# PROC106B_CAN_INTERFACE.net
KiCad netlist of a schematic drawn in Altium Designer
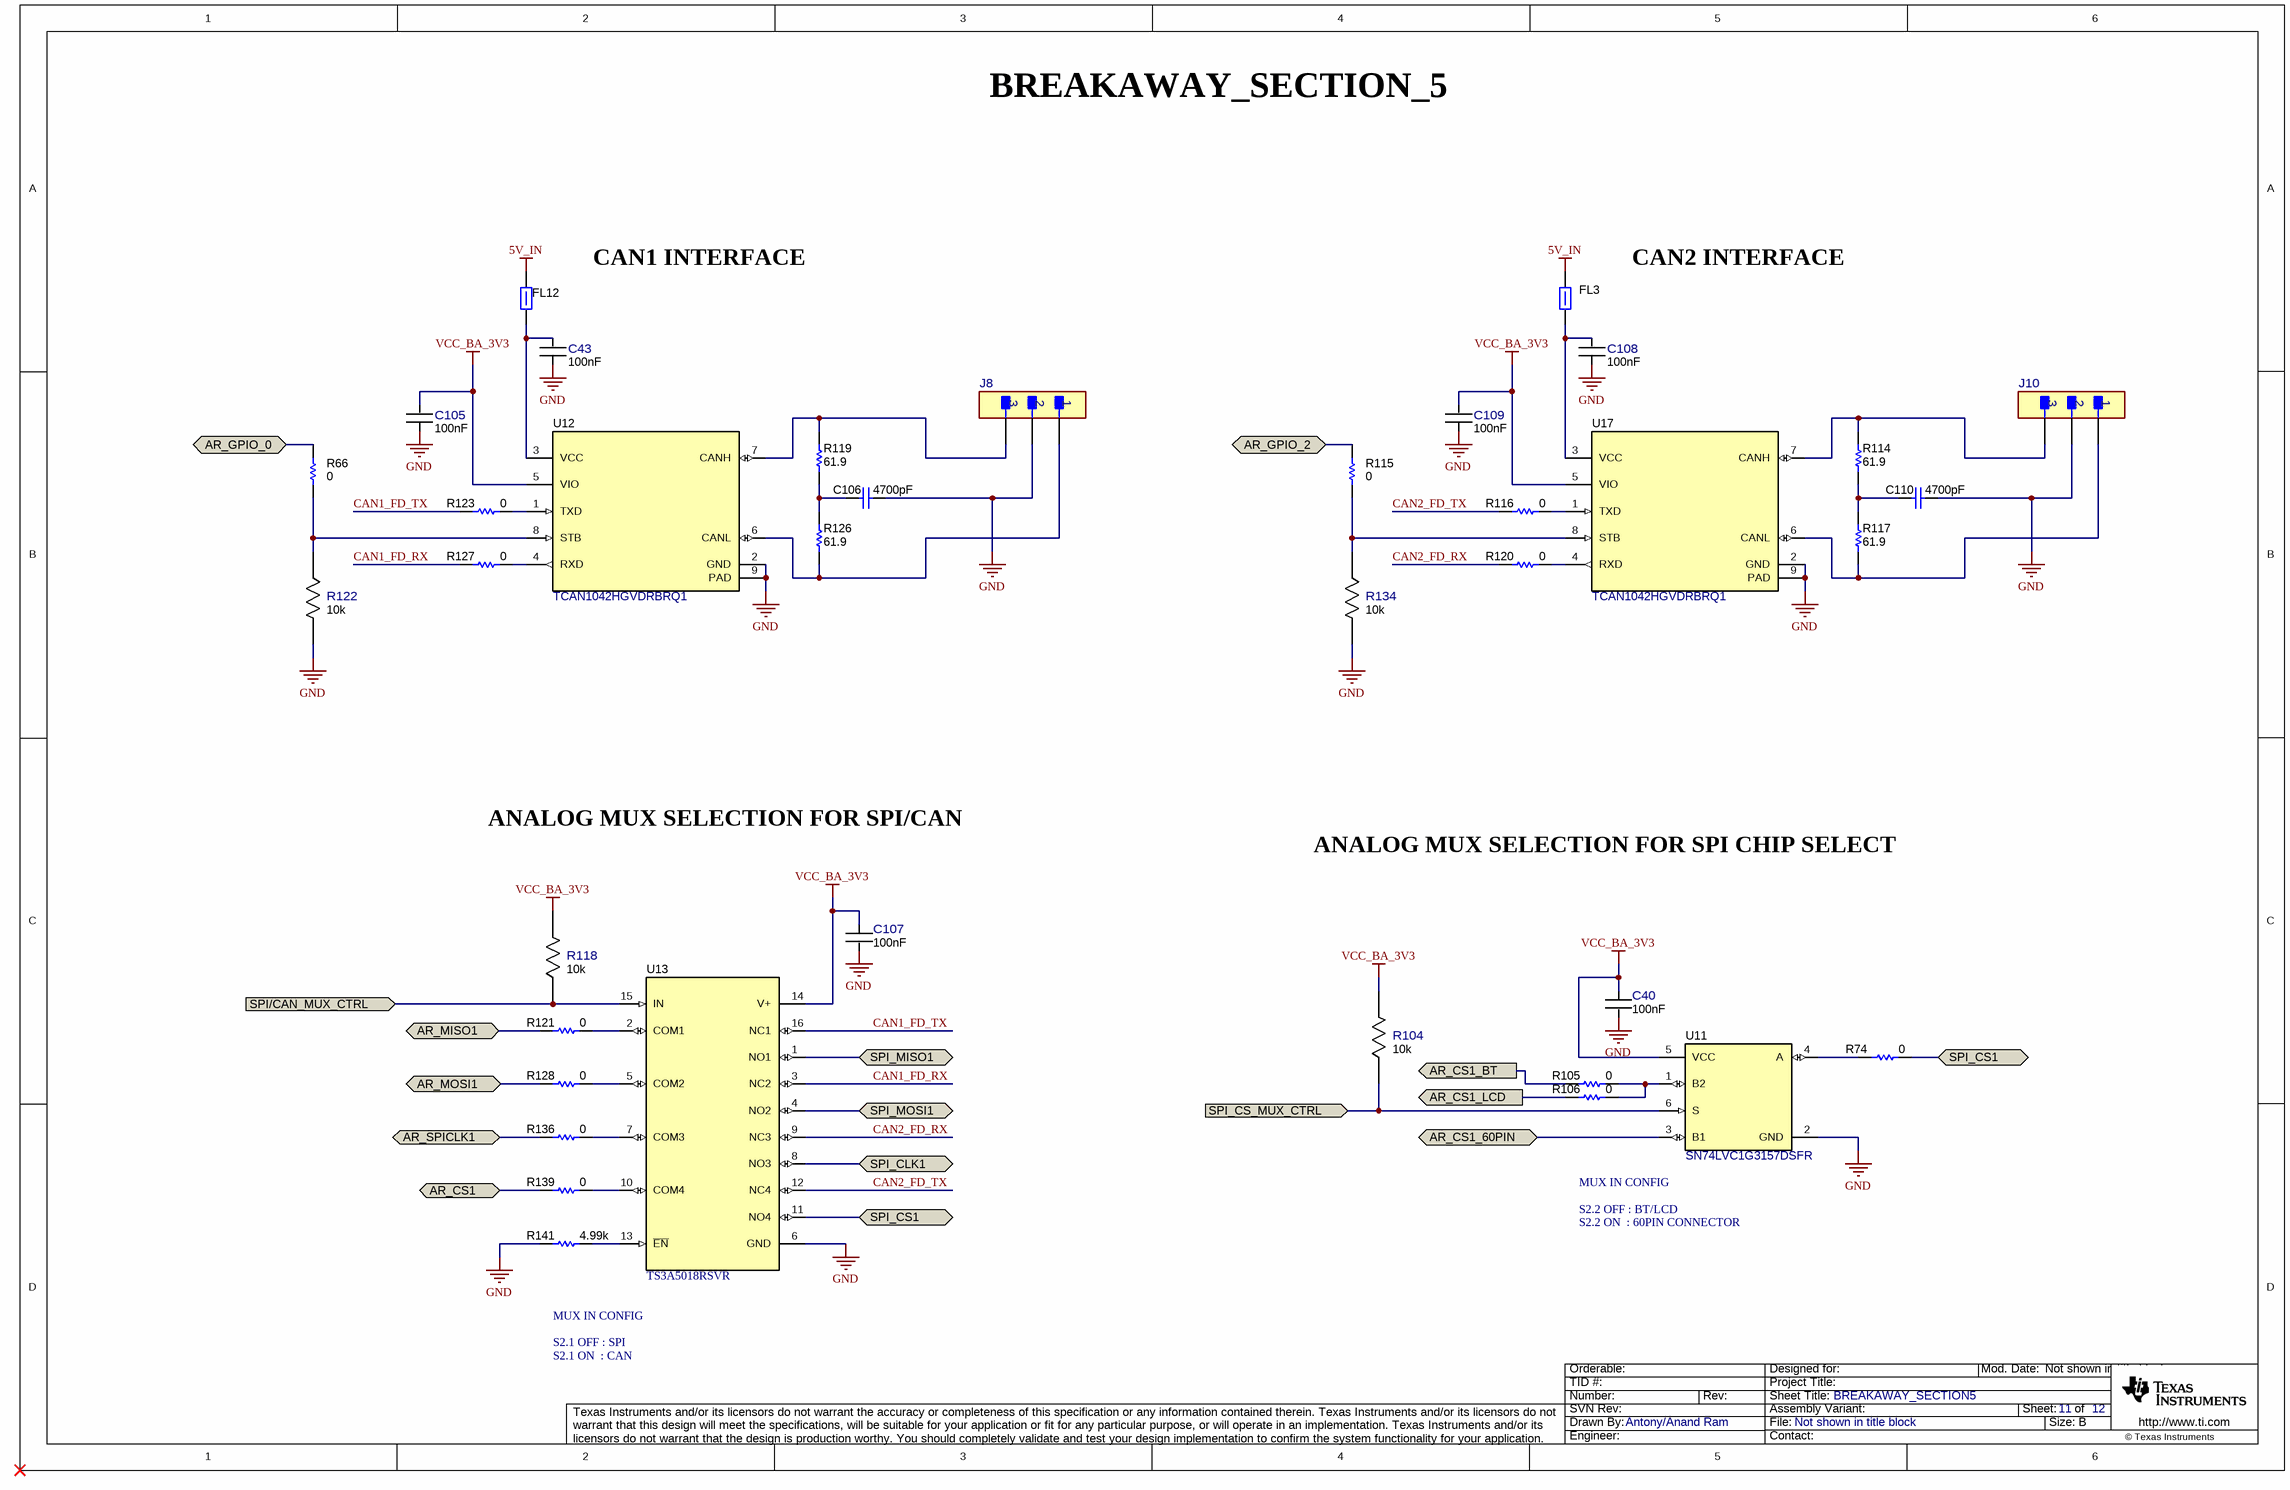
[diagram p0: PROC106B_CAN_INTERFACE.SchDoc]

(export (version "E")
  (design (tool "Eeschema 10.0.6"))
  (components
    (comp (ref "C40")
      (value "GRM033R6YA104KE14D")
      (footprint "FP-GRM033R6YA104KE14D_0201 (0603 Metric)-IPC_C")
      (description "Cap Ceramic 0.1uF 35V X5R 10% Pad SMD 0201 85C T/R")
      (fields (field (name "CAP_F") "100nF") (field (name "MANUFACTURER") "Murata Electronics North America"))
      (libsource (lib "Altium Vault - TI") (part "SYM-B32642B0223J"))
    )
    (comp (ref "C43")
      (value "GRM033R6YA104KE14D")
      (footprint "FP-GRM033R6YA104KE14D_0201 (0603 Metric)-IPC_C")
      (description "Cap Ceramic 0.1uF 35V X5R 10% Pad SMD 0201 85C T/R")
      (fields (field (name "CAP_F") "100nF") (field (name "MANUFACTURER") "Murata Electronics North America"))
      (libsource (lib "Altium Vault - TI") (part "SYM-B32642B0223J"))
    )
    (comp (ref "C105")
      (value "GRM033R6YA104KE14D")
      (footprint "FP-GRM033R6YA104KE14D_0201 (0603 Metric)-IPC_C")
      (description "Cap Ceramic 0.1uF 35V X5R 10% Pad SMD 0201 85C T/R")
      (fields (field (name "CAP_F") "100nF") (field (name "MANUFACTURER") "Murata Electronics North America"))
      (libsource (lib "Altium Vault - TI") (part "SYM-B32642B0223J"))
    )
    (comp (ref "C106")
      (value "GRM155R71H472KA01D")
      (footprint "0402L")
      (description "CAP, CERM, 4700 pF, 50 V, +/- 10%, X7R, 0402")
      (fields
        (field (name "MANUFACTURER") "MuRata")
        (field (name "VALUEDISPLAYED") "4700pF")
        (field (name "PUBLISHER") "Texas Instruments")
      )
      (libsource (lib "Altium Vault - TI") (part "Capacitor"))
    )
    (comp (ref "C107")
      (value "GRM033R6YA104KE14D")
      (footprint "FP-GRM033R6YA104KE14D_0201 (0603 Metric)-IPC_C")
      (description "Cap Ceramic 0.1uF 35V X5R 10% Pad SMD 0201 85C T/R")
      (fields (field (name "CAP_F") "100nF") (field (name "MANUFACTURER") "Murata Electronics North America"))
      (libsource (lib "Altium Vault - TI") (part "SYM-B32642B0223J"))
    )
    (comp (ref "C108")
      (value "GRM033R6YA104KE14D")
      (footprint "FP-GRM033R6YA104KE14D_0201 (0603 Metric)-IPC_C")
      (description "Cap Ceramic 0.1uF 35V X5R 10% Pad SMD 0201 85C T/R")
      (fields (field (name "CAP_F") "100nF") (field (name "MANUFACTURER") "Murata Electronics North America"))
      (libsource (lib "Altium Vault - TI") (part "SYM-B32642B0223J"))
    )
    (comp (ref "C109")
      (value "GRM033R6YA104KE14D")
      (footprint "FP-GRM033R6YA104KE14D_0201 (0603 Metric)-IPC_C")
      (description "Cap Ceramic 0.1uF 35V X5R 10% Pad SMD 0201 85C T/R")
      (fields (field (name "CAP_F") "100nF") (field (name "MANUFACTURER") "Murata Electronics North America"))
      (libsource (lib "Altium Vault - TI") (part "SYM-B32642B0223J"))
    )
    (comp (ref "C110")
      (value "GRM155R71H472KA01D")
      (footprint "0402L")
      (description "CAP, CERM, 4700 pF, 50 V, +/- 10%, X7R, 0402")
      (fields
        (field (name "MANUFACTURER") "MuRata")
        (field (name "VALUEDISPLAYED") "4700pF")
        (field (name "PUBLISHER") "Texas Instruments")
      )
      (libsource (lib "Altium Vault - TI") (part "Capacitor"))
    )
    (comp (ref "FL3")
      (value "BLM15PD300SZ1D")
      (footprint "0402L")
      (description "Inductor, Ferrite Bead, Ferrite, 2.2 A, 0.035 ohm, AEC-Q200 Grade 1, SMD")
      (fields (field (name "MANUFACTURER") "MuRata") (field (name "PUBLISHER") "Texas Instruments"))
      (libsource (lib "Altium Vault - TI") (part "Ferrite_Bead"))
    )
    (comp (ref "FL12")
      (value "BLM15PD300SZ1D")
      (footprint "0402L")
      (description "Inductor, Ferrite Bead, Ferrite, 2.2 A, 0.035 ohm, AEC-Q200 Grade 1, SMD")
      (fields (field (name "MANUFACTURER") "MuRata") (field (name "PUBLISHER") "Texas Instruments"))
      (libsource (lib "Altium Vault - TI") (part "Ferrite_Bead"))
    )
    (comp (ref "J8")
      (value "M50-3930342")
      (footprint "FP-M50-3930342_HDR3-MFG")
      (description "CONN HEADER R/A 3POS 1.27MM")
      (fields (field (name "MANUFACTURER") "Harwin"))
      (libsource (lib "Altium Vault - TI") (part "SYM-M50-3930342"))
    )
    (comp (ref "J10")
      (value "M50-3930342")
      (footprint "FP-M50-3930342_HDR3-MFG")
      (description "CONN HEADER R/A 3POS 1.27MM")
      (fields (field (name "MANUFACTURER") "Harwin"))
      (libsource (lib "Altium Vault - TI") (part "SYM-M50-3930342"))
    )
    (comp (ref "R66")
      (value "RC0201JR-070RL")
      (footprint "FP-RC0201JR-070RL_0201 (0603 Metric)-IPC_C")
      (description "RES SMD 0 OHM JUMPER 1/20W 0201")
      (fields (field (name "MANUFACTURER") "Yageo") (field (name "RES_OHM") "0"))
      (libsource (lib "Altium Vault - TI") (part "SYM-WSR3R1500F"))
    )
    (comp (ref "R74")
      (value "RC0201JR-070RL")
      (footprint "FP-RC0201JR-070RL_0201 (0603 Metric)-IPC_C")
      (description "RES SMD 0 OHM JUMPER 1/20W 0201")
      (fields (field (name "MANUFACTURER") "Yageo") (field (name "RES_OHM") "0"))
      (libsource (lib "Altium Vault - TI") (part "SYM-WSR3R1500F"))
    )
    (comp (ref "R104")
      (value "RR0306P-103-D")
      (footprint "FP-RR0306P-103-D_0201-IPC_C")
      (description "10 kOhms ±0.5% 0.05W, 1/20W Chip Resistor 0201 (0603 Metric)  Thin Film")
      (fields (field (name "MANUFACTURER") "Susumu") (field (name "RES_OHM") "10k"))
      (libsource (lib "Altium Vault - TI") (part "SYM-PMR18EZPJ000"))
    )
    (comp (ref "R105")
      (value "RC0201JR-070RL")
      (footprint "FP-RC0201JR-070RL_0201 (0603 Metric)-IPC_C")
      (description "RES SMD 0 OHM JUMPER 1/20W 0201")
      (fields (field (name "MANUFACTURER") "Yageo") (field (name "RES_OHM") "0"))
      (libsource (lib "Altium Vault - TI") (part "SYM-WSR3R1500F"))
    )
    (comp (ref "R106")
      (value "RC0201JR-070RL")
      (footprint "FP-RC0201JR-070RL_0201 (0603 Metric)-IPC_C")
      (description "RES SMD 0 OHM JUMPER 1/20W 0201")
      (fields (field (name "MANUFACTURER") "Yageo") (field (name "RES_OHM") "0"))
      (libsource (lib "Altium Vault - TI") (part "SYM-WSR3R1500F"))
    )
    (comp (ref "R114")
      (value "CRCW040261R9FKED")
      (footprint "0402L")
      (description "RES, 61.9, 1%, 0.063 W, AEC-Q200 Grade 0, 0402")
      (fields (field (name "MANUFACTURER") "Vishay-Dale") (field (name "VALUEDISPLAYED") "61.9"))
      (libsource (lib "Altium Vault - TI") (part "Resistor"))
    )
    (comp (ref "R115")
      (value "RC0201JR-070RL")
      (footprint "FP-RC0201JR-070RL_0201 (0603 Metric)-IPC_C")
      (description "RES SMD 0 OHM JUMPER 1/20W 0201")
      (fields (field (name "MANUFACTURER") "Yageo") (field (name "RES_OHM") "0"))
      (libsource (lib "Altium Vault - TI") (part "SYM-WSR3R1500F"))
    )
    (comp (ref "R116")
      (value "RC0201JR-070RL")
      (footprint "FP-RC0201JR-070RL_0201 (0603 Metric)-IPC_C")
      (description "RES SMD 0 OHM JUMPER 1/20W 0201")
      (fields (field (name "MANUFACTURER") "Yageo") (field (name "RES_OHM") "0"))
      (libsource (lib "Altium Vault - TI") (part "SYM-WSR3R1500F"))
    )
    (comp (ref "R117")
      (value "CRCW040261R9FKED")
      (footprint "0402L")
      (description "RES, 61.9, 1%, 0.063 W, AEC-Q200 Grade 0, 0402")
      (fields (field (name "MANUFACTURER") "Vishay-Dale") (field (name "VALUEDISPLAYED") "61.9"))
      (libsource (lib "Altium Vault - TI") (part "Resistor"))
    )
    (comp (ref "R118")
      (value "RR0306P-103-D")
      (footprint "FP-RR0306P-103-D_0201-IPC_C")
      (description "10 kOhms ±0.5% 0.05W, 1/20W Chip Resistor 0201 (0603 Metric)  Thin Film")
      (fields (field (name "MANUFACTURER") "Susumu") (field (name "RES_OHM") "10k"))
      (libsource (lib "Altium Vault - TI") (part "SYM-PMR18EZPJ000"))
    )
    (comp (ref "R119")
      (value "CRCW040261R9FKED")
      (footprint "0402L")
      (description "RES, 61.9, 1%, 0.063 W, AEC-Q200 Grade 0, 0402")
      (fields (field (name "MANUFACTURER") "Vishay-Dale") (field (name "VALUEDISPLAYED") "61.9"))
      (libsource (lib "Altium Vault - TI") (part "Resistor"))
    )
    (comp (ref "R120")
      (value "RC0201JR-070RL")
      (footprint "FP-RC0201JR-070RL_0201 (0603 Metric)-IPC_C")
      (description "RES SMD 0 OHM JUMPER 1/20W 0201")
      (fields (field (name "MANUFACTURER") "Yageo") (field (name "RES_OHM") "0"))
      (libsource (lib "Altium Vault - TI") (part "SYM-WSR3R1500F"))
    )
    (comp (ref "R121")
      (value "RC0201JR-070RL")
      (footprint "FP-RC0201JR-070RL_0201 (0603 Metric)-IPC_C")
      (description "RES SMD 0 OHM JUMPER 1/20W 0201")
      (fields (field (name "MANUFACTURER") "Yageo") (field (name "RES_OHM") "0"))
      (libsource (lib "Altium Vault - TI") (part "SYM-WSR3R1500F"))
    )
    (comp (ref "R122")
      (value "RR0306P-103-D")
      (footprint "FP-RR0306P-103-D_0201-IPC_C")
      (description "10 kOhms ±0.5% 0.05W, 1/20W Chip Resistor 0201 (0603 Metric)  Thin Film")
      (fields (field (name "MANUFACTURER") "Susumu") (field (name "RES_OHM") "10k"))
      (libsource (lib "Altium Vault - TI") (part "SYM-PMR18EZPJ000"))
    )
    (comp (ref "R123")
      (value "RC0201JR-070RL")
      (footprint "FP-RC0201JR-070RL_0201 (0603 Metric)-IPC_C")
      (description "RES SMD 0 OHM JUMPER 1/20W 0201")
      (fields (field (name "MANUFACTURER") "Yageo") (field (name "RES_OHM") "0"))
      (libsource (lib "Altium Vault - TI") (part "SYM-WSR3R1500F"))
    )
    (comp (ref "R126")
      (value "CRCW040261R9FKED")
      (footprint "0402L")
      (description "RES, 61.9, 1%, 0.063 W, AEC-Q200 Grade 0, 0402")
      (fields (field (name "MANUFACTURER") "Vishay-Dale") (field (name "VALUEDISPLAYED") "61.9"))
      (libsource (lib "Altium Vault - TI") (part "Resistor"))
    )
    (comp (ref "R127")
      (value "RC0201JR-070RL")
      (footprint "FP-RC0201JR-070RL_0201 (0603 Metric)-IPC_C")
      (description "RES SMD 0 OHM JUMPER 1/20W 0201")
      (fields (field (name "MANUFACTURER") "Yageo") (field (name "RES_OHM") "0"))
      (libsource (lib "Altium Vault - TI") (part "SYM-WSR3R1500F"))
    )
    (comp (ref "R128")
      (value "RC0201JR-070RL")
      (footprint "FP-RC0201JR-070RL_0201 (0603 Metric)-IPC_C")
      (description "RES SMD 0 OHM JUMPER 1/20W 0201")
      (fields (field (name "MANUFACTURER") "Yageo") (field (name "RES_OHM") "0"))
      (libsource (lib "Altium Vault - TI") (part "SYM-WSR3R1500F"))
    )
    (comp (ref "R134")
      (value "RR0306P-103-D")
      (footprint "FP-RR0306P-103-D_0201-IPC_C")
      (description "10 kOhms ±0.5% 0.05W, 1/20W Chip Resistor 0201 (0603 Metric)  Thin Film")
      (fields (field (name "MANUFACTURER") "Susumu") (field (name "RES_OHM") "10k"))
      (libsource (lib "Altium Vault - TI") (part "SYM-PMR18EZPJ000"))
    )
    (comp (ref "R136")
      (value "RC0201JR-070RL")
      (footprint "FP-RC0201JR-070RL_0201 (0603 Metric)-IPC_C")
      (description "RES SMD 0 OHM JUMPER 1/20W 0201")
      (fields (field (name "MANUFACTURER") "Yageo") (field (name "RES_OHM") "0"))
      (libsource (lib "Altium Vault - TI") (part "SYM-WSR3R1500F"))
    )
    (comp (ref "R139")
      (value "RC0201JR-070RL")
      (footprint "FP-RC0201JR-070RL_0201 (0603 Metric)-IPC_C")
      (description "RES SMD 0 OHM JUMPER 1/20W 0201")
      (fields (field (name "MANUFACTURER") "Yageo") (field (name "RES_OHM") "0"))
      (libsource (lib "Altium Vault - TI") (part "SYM-WSR3R1500F"))
    )
    (comp (ref "R141")
      (value "4.99k")
      (footprint "0201L")
      (description "RES, 4.99 k, 1%, 0.05 W, 0201")
      (fields
        (field (name "MANUFACTURER") "Yageo America")
        (field (name "PARTNUMBER") "RC0201FR-074K99L")
        (field (name "PUBLISHER") "Texas Instruments")
      )
      (libsource (lib "Altium Vault - TI") (part "Resistor"))
    )
    (comp (ref "U11")
      (value "SN74LVC1G3157DSFR")
      (footprint "DSF0006A")
      (description "1-Channel, 2:1 Analog Switch, DSF0006A (X2SON-6)")
      (fields
        (field (name "GENERIC PART NUMBER") "SN74LVC1G3157")
        (field (name "MANUFACTURER") "Texas Instruments")
      )
      (libsource (lib "Altium Vault - TI") (part "SN74LVC1G3157"))
    )
    (comp (ref "U12")
      (value "TCAN1042HGVDRBRQ1")
      (footprint "DRB0008F")
      (description "Automotive Fault Protected CAN Transceiver With Flexible Data-Rate, DRB0008F (VSON-8)")
      (fields
        (field (name "MANUFACTURER") "Texas Instruments")
        (field (name "ALTERNATE PARTNUMBER") "TCAN1042HGVDRBTQ1")
      )
      (libsource (lib "Altium Vault - TI") (part "TCAN1042DRB_V"))
    )
    (comp (ref "U13")
      (value "TS3A5018RSVR")
      (footprint "RSV0016A")
      (description "10-Ohm Quad SPDT Analog Switch, RSV0016A (UQFN-16)")
      (fields
        (field (name "MANUFACTURER") "Texas Instruments")
        (field (name "PARTNUMBER") "TS3A5018RSVR")
        (field (name "PUBLISHER") "Texas Instruments")
      )
      (libsource (lib "Altium Vault - TI") (part "TS3A5018RSV"))
    )
    (comp (ref "U17")
      (value "TCAN1042HGVDRBRQ1")
      (footprint "DRB0008F")
      (description "Automotive Fault Protected CAN Transceiver With Flexible Data-Rate, DRB0008F (VSON-8)")
      (fields
        (field (name "MANUFACTURER") "Texas Instruments")
        (field (name "ALTERNATE PARTNUMBER") "TCAN1042HGVDRBTQ1")
      )
      (libsource (lib "Altium Vault - TI") (part "TCAN1042DRB_V"))
    )
  )
  (nets
    (net (code "1") (name "/AR_CS1") (class "Default")
      (node (ref "R139") (pin "2") (pinfunction "2_2") (pintype "passive"))
    )
    (net (code "2") (name "/AR_CS1_60PIN") (class "Default")
      (node (ref "U11") (pin "3") (pinfunction "B1_3") (pintype "bidirectional"))
    )
    (net (code "3") (name "/AR_CS1_BT") (class "Default")
      (node (ref "R105") (pin "2") (pinfunction "2_2") (pintype "passive"))
    )
    (net (code "4") (name "/AR_CS1_LCD") (class "Default")
      (node (ref "R106") (pin "2") (pinfunction "2_2") (pintype "passive"))
    )
    (net (code "5") (name "/AR_GPIO_0") (class "Default")
      (node (ref "R66") (pin "1") (pinfunction "1_1") (pintype "passive"))
    )
    (net (code "6") (name "/AR_GPIO_2") (class "Default")
      (node (ref "R115") (pin "1") (pinfunction "1_1") (pintype "passive"))
    )
    (net (code "7") (name "/AR_MISO1") (class "Default")
      (node (ref "R121") (pin "2") (pinfunction "2_2") (pintype "passive"))
    )
    (net (code "8") (name "/AR_MOSI1") (class "Default")
      (node (ref "R128") (pin "2") (pinfunction "2_2") (pintype "passive"))
    )
    (net (code "9") (name "/AR_SPICLK1") (class "Default")
      (node (ref "R136") (pin "2") (pinfunction "2_2") (pintype "passive"))
    )
    (net (code "10") (name "/CAN1_FD_RX") (class "Default")
      (node (ref "R127") (pin "2") (pinfunction "2_2") (pintype "passive"))
      (node (ref "U13") (pin "3") (pinfunction "NC2_3") (pintype "bidirectional"))
    )
    (net (code "11") (name "/CAN1_FD_TX") (class "Default")
      (node (ref "R123") (pin "2") (pinfunction "2_2") (pintype "passive"))
      (node (ref "U13") (pin "16") (pinfunction "NC1_16") (pintype "bidirectional"))
    )
    (net (code "12") (name "/CAN2_FD_RX") (class "Default")
      (node (ref "R120") (pin "2") (pinfunction "2_2") (pintype "passive"))
      (node (ref "U13") (pin "9") (pinfunction "NC3_9") (pintype "bidirectional"))
    )
    (net (code "13") (name "/CAN2_FD_TX") (class "Default")
      (node (ref "R116") (pin "2") (pinfunction "2_2") (pintype "passive"))
      (node (ref "U13") (pin "12") (pinfunction "NC4_12") (pintype "bidirectional"))
    )
    (net (code "14") (name "/SPI_CLK1") (class "Default")
      (node (ref "U13") (pin "8") (pinfunction "NO3_8") (pintype "bidirectional"))
    )
    (net (code "15") (name "/SPI_CS1") (class "Default")
      (node (ref "R74") (pin "1") (pinfunction "1_1") (pintype "passive"))
      (node (ref "U13") (pin "11") (pinfunction "NO4_11") (pintype "bidirectional"))
    )
    (net (code "16") (name "/SPI_CS_MUX_CTRL") (class "Default")
      (node (ref "R104") (pin "1") (pinfunction "1_1") (pintype "passive"))
      (node (ref "U11") (pin "6") (pinfunction "S_6") (pintype "input"))
    )
    (net (code "17") (name "/SPI_MISO1") (class "Default")
      (node (ref "U13") (pin "1") (pinfunction "NO1_1") (pintype "bidirectional"))
    )
    (net (code "18") (name "/SPI_MOSI1") (class "Default")
      (node (ref "U13") (pin "4") (pinfunction "NO2_4") (pintype "bidirectional"))
    )
    (net (code "19") (name "/SPI{slash}CAN_MUX_CTRL") (class "Default")
      (node (ref "R118") (pin "1") (pinfunction "1_1") (pintype "passive"))
      (node (ref "U13") (pin "15") (pinfunction "IN_15") (pintype "input"))
    )
    (net (code "20") (name "5V_IN") (class "Default")
      (node (ref "FL12") (pin "2") (pinfunction "2_2") (pintype "passive"))
      (node (ref "FL3") (pin "2") (pinfunction "2_2") (pintype "passive"))
    )
    (net (code "21") (name "GND") (class "Default")
      (node (ref "C105") (pin "1") (pinfunction "1_1") (pintype "passive"))
      (node (ref "C106") (pin "1") (pinfunction "1_1") (pintype "passive"))
      (node (ref "C107") (pin "2") (pinfunction "2_2") (pintype "passive"))
      (node (ref "C108") (pin "1") (pinfunction "1_1") (pintype "passive"))
      (node (ref "C109") (pin "1") (pinfunction "1_1") (pintype "passive"))
      (node (ref "C110") (pin "1") (pinfunction "1_1") (pintype "passive"))
      (node (ref "C40") (pin "2") (pinfunction "2_2") (pintype "passive"))
      (node (ref "C43") (pin "1") (pinfunction "1_1") (pintype "passive"))
      (node (ref "J10") (pin "2") (pinfunction "2_2") (pintype "passive"))
      (node (ref "J8") (pin "2") (pinfunction "2_2") (pintype "passive"))
      (node (ref "R122") (pin "2") (pinfunction "2_2") (pintype "passive"))
      (node (ref "R134") (pin "2") (pinfunction "2_2") (pintype "passive"))
      (node (ref "R141") (pin "2") (pinfunction "2_2") (pintype "passive"))
      (node (ref "U11") (pin "2") (pinfunction "GND_2") (pintype "power_in"))
      (node (ref "U12") (pin "2") (pinfunction "GND_2") (pintype "power_in"))
      (node (ref "U12") (pin "9") (pinfunction "PAD_9") (pintype "power_in"))
      (node (ref "U13") (pin "6") (pinfunction "GND_6") (pintype "power_in"))
      (node (ref "U17") (pin "2") (pinfunction "GND_2") (pintype "power_in"))
      (node (ref "U17") (pin "9") (pinfunction "PAD_9") (pintype "power_in"))
    )
    (net (code "22") (name "Net-(C106-Pad2)") (class "Default")
      (node (ref "C106") (pin "2") (pinfunction "2_2") (pintype "passive"))
      (node (ref "R119") (pin "1") (pinfunction "1_1") (pintype "passive"))
      (node (ref "R126") (pin "2") (pinfunction "2_2") (pintype "passive"))
    )
    (net (code "23") (name "Net-(C110-Pad2)") (class "Default")
      (node (ref "C110") (pin "2") (pinfunction "2_2") (pintype "passive"))
      (node (ref "R114") (pin "1") (pinfunction "1_1") (pintype "passive"))
      (node (ref "R117") (pin "2") (pinfunction "2_2") (pintype "passive"))
    )
    (net (code "24") (name "Net-(U11-A)") (class "Default")
      (node (ref "R74") (pin "2") (pinfunction "2_2") (pintype "passive"))
      (node (ref "U11") (pin "4") (pinfunction "A_4") (pintype "bidirectional"))
    )
    (net (code "25") (name "Net-(U11-B2)") (class "Default")
      (node (ref "R105") (pin "1") (pinfunction "1_1") (pintype "passive"))
      (node (ref "R106") (pin "1") (pinfunction "1_1") (pintype "passive"))
      (node (ref "U11") (pin "1") (pinfunction "B2_1") (pintype "bidirectional"))
    )
    (net (code "26") (name "Net-(U12-CANH)") (class "Default")
      (node (ref "J8") (pin "3") (pinfunction "3_3") (pintype "passive"))
      (node (ref "R119") (pin "2") (pinfunction "2_2") (pintype "passive"))
      (node (ref "U12") (pin "7") (pinfunction "CANH_7") (pintype "bidirectional"))
    )
    (net (code "27") (name "Net-(U12-CANL)") (class "Default")
      (node (ref "J8") (pin "1") (pinfunction "1_1") (pintype "passive"))
      (node (ref "R126") (pin "1") (pinfunction "1_1") (pintype "passive"))
      (node (ref "U12") (pin "6") (pinfunction "CANL_6") (pintype "bidirectional"))
    )
    (net (code "28") (name "Net-(U12-RXD)") (class "Default")
      (node (ref "R127") (pin "1") (pinfunction "1_1") (pintype "passive"))
      (node (ref "U12") (pin "4") (pinfunction "RXD_4") (pintype "output"))
    )
    (net (code "29") (name "Net-(U12-STB)") (class "Default")
      (node (ref "R122") (pin "1") (pinfunction "1_1") (pintype "passive"))
      (node (ref "R66") (pin "2") (pinfunction "2_2") (pintype "passive"))
      (node (ref "U12") (pin "8") (pinfunction "STB_8") (pintype "input"))
    )
    (net (code "30") (name "Net-(U12-TXD)") (class "Default")
      (node (ref "R123") (pin "1") (pinfunction "1_1") (pintype "passive"))
      (node (ref "U12") (pin "1") (pinfunction "TXD_1") (pintype "input"))
    )
    (net (code "31") (name "Net-(U12-VCC)") (class "Default")
      (node (ref "C43") (pin "2") (pinfunction "2_2") (pintype "passive"))
      (node (ref "FL12") (pin "1") (pinfunction "1_1") (pintype "passive"))
      (node (ref "U12") (pin "3") (pinfunction "VCC_3") (pintype "power_in"))
    )
    (net (code "32") (name "Net-(U13-COM1)") (class "Default")
      (node (ref "R121") (pin "1") (pinfunction "1_1") (pintype "passive"))
      (node (ref "U13") (pin "2") (pinfunction "COM1_2") (pintype "bidirectional"))
    )
    (net (code "33") (name "Net-(U13-COM2)") (class "Default")
      (node (ref "R128") (pin "1") (pinfunction "1_1") (pintype "passive"))
      (node (ref "U13") (pin "5") (pinfunction "COM2_5") (pintype "bidirectional"))
    )
    (net (code "34") (name "Net-(U13-COM3)") (class "Default")
      (node (ref "R136") (pin "1") (pinfunction "1_1") (pintype "passive"))
      (node (ref "U13") (pin "7") (pinfunction "COM3_7") (pintype "bidirectional"))
    )
    (net (code "35") (name "Net-(U13-COM4)") (class "Default")
      (node (ref "R139") (pin "1") (pinfunction "1_1") (pintype "passive"))
      (node (ref "U13") (pin "10") (pinfunction "COM4_10") (pintype "bidirectional"))
    )
    (net (code "36") (name "Net-(U13-EN)") (class "Default")
      (node (ref "R141") (pin "1") (pinfunction "1_1") (pintype "passive"))
      (node (ref "U13") (pin "13") (pinfunction "EN_13") (pintype "input"))
    )
    (net (code "37") (name "Net-(U17-CANH)") (class "Default")
      (node (ref "J10") (pin "3") (pinfunction "3_3") (pintype "passive"))
      (node (ref "R114") (pin "2") (pinfunction "2_2") (pintype "passive"))
      (node (ref "U17") (pin "7") (pinfunction "CANH_7") (pintype "bidirectional"))
    )
    (net (code "38") (name "Net-(U17-CANL)") (class "Default")
      (node (ref "J10") (pin "1") (pinfunction "1_1") (pintype "passive"))
      (node (ref "R117") (pin "1") (pinfunction "1_1") (pintype "passive"))
      (node (ref "U17") (pin "6") (pinfunction "CANL_6") (pintype "bidirectional"))
    )
    (net (code "39") (name "Net-(U17-RXD)") (class "Default")
      (node (ref "R120") (pin "1") (pinfunction "1_1") (pintype "passive"))
      (node (ref "U17") (pin "4") (pinfunction "RXD_4") (pintype "output"))
    )
    (net (code "40") (name "Net-(U17-STB)") (class "Default")
      (node (ref "R115") (pin "2") (pinfunction "2_2") (pintype "passive"))
      (node (ref "R134") (pin "1") (pinfunction "1_1") (pintype "passive"))
      (node (ref "U17") (pin "8") (pinfunction "STB_8") (pintype "input"))
    )
    (net (code "41") (name "Net-(U17-TXD)") (class "Default")
      (node (ref "R116") (pin "1") (pinfunction "1_1") (pintype "passive"))
      (node (ref "U17") (pin "1") (pinfunction "TXD_1") (pintype "input"))
    )
    (net (code "42") (name "Net-(U17-VCC)") (class "Default")
      (node (ref "C108") (pin "2") (pinfunction "2_2") (pintype "passive"))
      (node (ref "FL3") (pin "1") (pinfunction "1_1") (pintype "passive"))
      (node (ref "U17") (pin "3") (pinfunction "VCC_3") (pintype "power_in"))
    )
    (net (code "43") (name "VCC_BA_3V3") (class "Default")
      (node (ref "C105") (pin "2") (pinfunction "2_2") (pintype "passive"))
      (node (ref "C107") (pin "1") (pinfunction "1_1") (pintype "passive"))
      (node (ref "C109") (pin "2") (pinfunction "2_2") (pintype "passive"))
      (node (ref "C40") (pin "1") (pinfunction "1_1") (pintype "passive"))
      (node (ref "R104") (pin "2") (pinfunction "2_2") (pintype "passive"))
      (node (ref "R118") (pin "2") (pinfunction "2_2") (pintype "passive"))
      (node (ref "U11") (pin "5") (pinfunction "VCC_5") (pintype "power_in"))
      (node (ref "U12") (pin "5") (pinfunction "VIO_5") (pintype "power_in"))
      (node (ref "U13") (pin "14") (pinfunction "V+_14") (pintype "power_in"))
      (node (ref "U17") (pin "5") (pinfunction "VIO_5") (pintype "power_in"))
    )
  )
)
